# Nut-nhan.net
KiCad netlist of a schematic drawn in Altium Designer
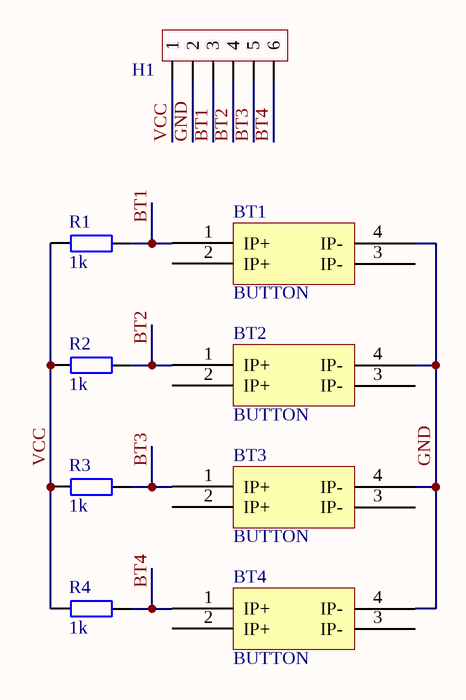
[diagram p0: Nut-nhan.SchDoc]

(export (version "E")
  (design (tool "Eeschema 10.0.6"))
  (components
    (comp (ref "BT1")
      (value "BUTTON")
      (footprint "BUTTON4")
      (libsource (lib "THU_VIEN_PQB_Schlib1") (part "BUTTON4"))
    )
    (comp (ref "BT2")
      (value "BUTTON")
      (footprint "BUTTON4")
      (libsource (lib "THU_VIEN_PQB_Schlib1") (part "BUTTON4"))
    )
    (comp (ref "BT3")
      (value "BUTTON")
      (footprint "BUTTON4")
      (libsource (lib "THU_VIEN_PQB_Schlib1") (part "BUTTON4"))
    )
    (comp (ref "BT4")
      (value "BUTTON")
      (footprint "BUTTON4")
      (libsource (lib "THU_VIEN_PQB_Schlib1") (part "BUTTON4"))
    )
    (comp (ref "H1")
      (value "Header6")
      (footprint "HDR6")
      (description "Header IDC, 6 x 1 Pin Vertical 2.54mm Pitch (Non-Boxed, Male)")
      (libsource (lib "LIBRARY") (part "Header6"))
    )
    (comp (ref "R1")
      (value "1k")
      (footprint "R1/4W")
      (description "Resistor 1/4W")
      (libsource (lib "syhaunguyen") (part "R1/4W"))
    )
    (comp (ref "R2")
      (value "1k")
      (footprint "R1/4W")
      (description "Resistor 1/4W")
      (libsource (lib "syhaunguyen") (part "R1/4W"))
    )
    (comp (ref "R3")
      (value "1k")
      (footprint "R1/4W")
      (description "Resistor 1/4W")
      (libsource (lib "syhaunguyen") (part "R1/4W"))
    )
    (comp (ref "R4")
      (value "1k")
      (footprint "R1/4W")
      (description "Resistor 1/4W")
      (libsource (lib "syhaunguyen") (part "R1/4W"))
    )
  )
  (nets
    (net (code "1") (name "/BT1") (class "Default")
      (node (ref "BT1") (pin "1") (pinfunction "IP+_1") (pintype "passive"))
      (node (ref "H1") (pin "3") (pinfunction "3_3") (pintype "passive"))
      (node (ref "R1") (pin "2") (pinfunction "2_2") (pintype "passive"))
    )
    (net (code "2") (name "/BT2") (class "Default")
      (node (ref "BT2") (pin "1") (pinfunction "IP+_1") (pintype "passive"))
      (node (ref "H1") (pin "4") (pinfunction "4_4") (pintype "passive"))
      (node (ref "R2") (pin "2") (pinfunction "2_2") (pintype "passive"))
    )
    (net (code "3") (name "/BT3") (class "Default")
      (node (ref "BT3") (pin "1") (pinfunction "IP+_1") (pintype "passive"))
      (node (ref "H1") (pin "5") (pinfunction "5_5") (pintype "passive"))
      (node (ref "R3") (pin "2") (pinfunction "2_2") (pintype "passive"))
    )
    (net (code "4") (name "/BT4") (class "Default")
      (node (ref "BT4") (pin "1") (pinfunction "IP+_1") (pintype "passive"))
      (node (ref "H1") (pin "6") (pinfunction "6_6") (pintype "passive"))
      (node (ref "R4") (pin "2") (pinfunction "2_2") (pintype "passive"))
    )
    (net (code "5") (name "/GND") (class "Default")
      (node (ref "BT1") (pin "4") (pinfunction "IP-_4") (pintype "passive"))
      (node (ref "BT2") (pin "4") (pinfunction "IP-_4") (pintype "passive"))
      (node (ref "BT3") (pin "4") (pinfunction "IP-_4") (pintype "passive"))
      (node (ref "BT4") (pin "4") (pinfunction "IP-_4") (pintype "passive"))
      (node (ref "H1") (pin "2") (pinfunction "2_2") (pintype "passive"))
    )
    (net (code "6") (name "/VCC") (class "Default")
      (node (ref "H1") (pin "1") (pinfunction "1_1") (pintype "passive"))
      (node (ref "R1") (pin "1") (pinfunction "1_1") (pintype "passive"))
      (node (ref "R2") (pin "1") (pinfunction "1_1") (pintype "passive"))
      (node (ref "R3") (pin "1") (pinfunction "1_1") (pintype "passive"))
      (node (ref "R4") (pin "1") (pinfunction "1_1") (pintype "passive"))
    )
    (net (code "7") (name "unconnected-(BT1-IP+-Pad2)") (class "Default")
      (node (ref "BT1") (pin "2") (pinfunction "IP+_2") (pintype "passive"))
    )
    (net (code "8") (name "unconnected-(BT1-IP--Pad3)") (class "Default")
      (node (ref "BT1") (pin "3") (pinfunction "IP-_3") (pintype "passive"))
    )
    (net (code "9") (name "unconnected-(BT2-IP+-Pad2)") (class "Default")
      (node (ref "BT2") (pin "2") (pinfunction "IP+_2") (pintype "passive"))
    )
    (net (code "10") (name "unconnected-(BT2-IP--Pad3)") (class "Default")
      (node (ref "BT2") (pin "3") (pinfunction "IP-_3") (pintype "passive"))
    )
    (net (code "11") (name "unconnected-(BT3-IP+-Pad2)") (class "Default")
      (node (ref "BT3") (pin "2") (pinfunction "IP+_2") (pintype "passive"))
    )
    (net (code "12") (name "unconnected-(BT3-IP--Pad3)") (class "Default")
      (node (ref "BT3") (pin "3") (pinfunction "IP-_3") (pintype "passive"))
    )
    (net (code "13") (name "unconnected-(BT4-IP+-Pad2)") (class "Default")
      (node (ref "BT4") (pin "2") (pinfunction "IP+_2") (pintype "passive"))
    )
    (net (code "14") (name "unconnected-(BT4-IP--Pad3)") (class "Default")
      (node (ref "BT4") (pin "3") (pinfunction "IP-_3") (pintype "passive"))
    )
  )
)
